# Terrarium_Schematic.net
KiCad netlist of a schematic drawn in EAGLE
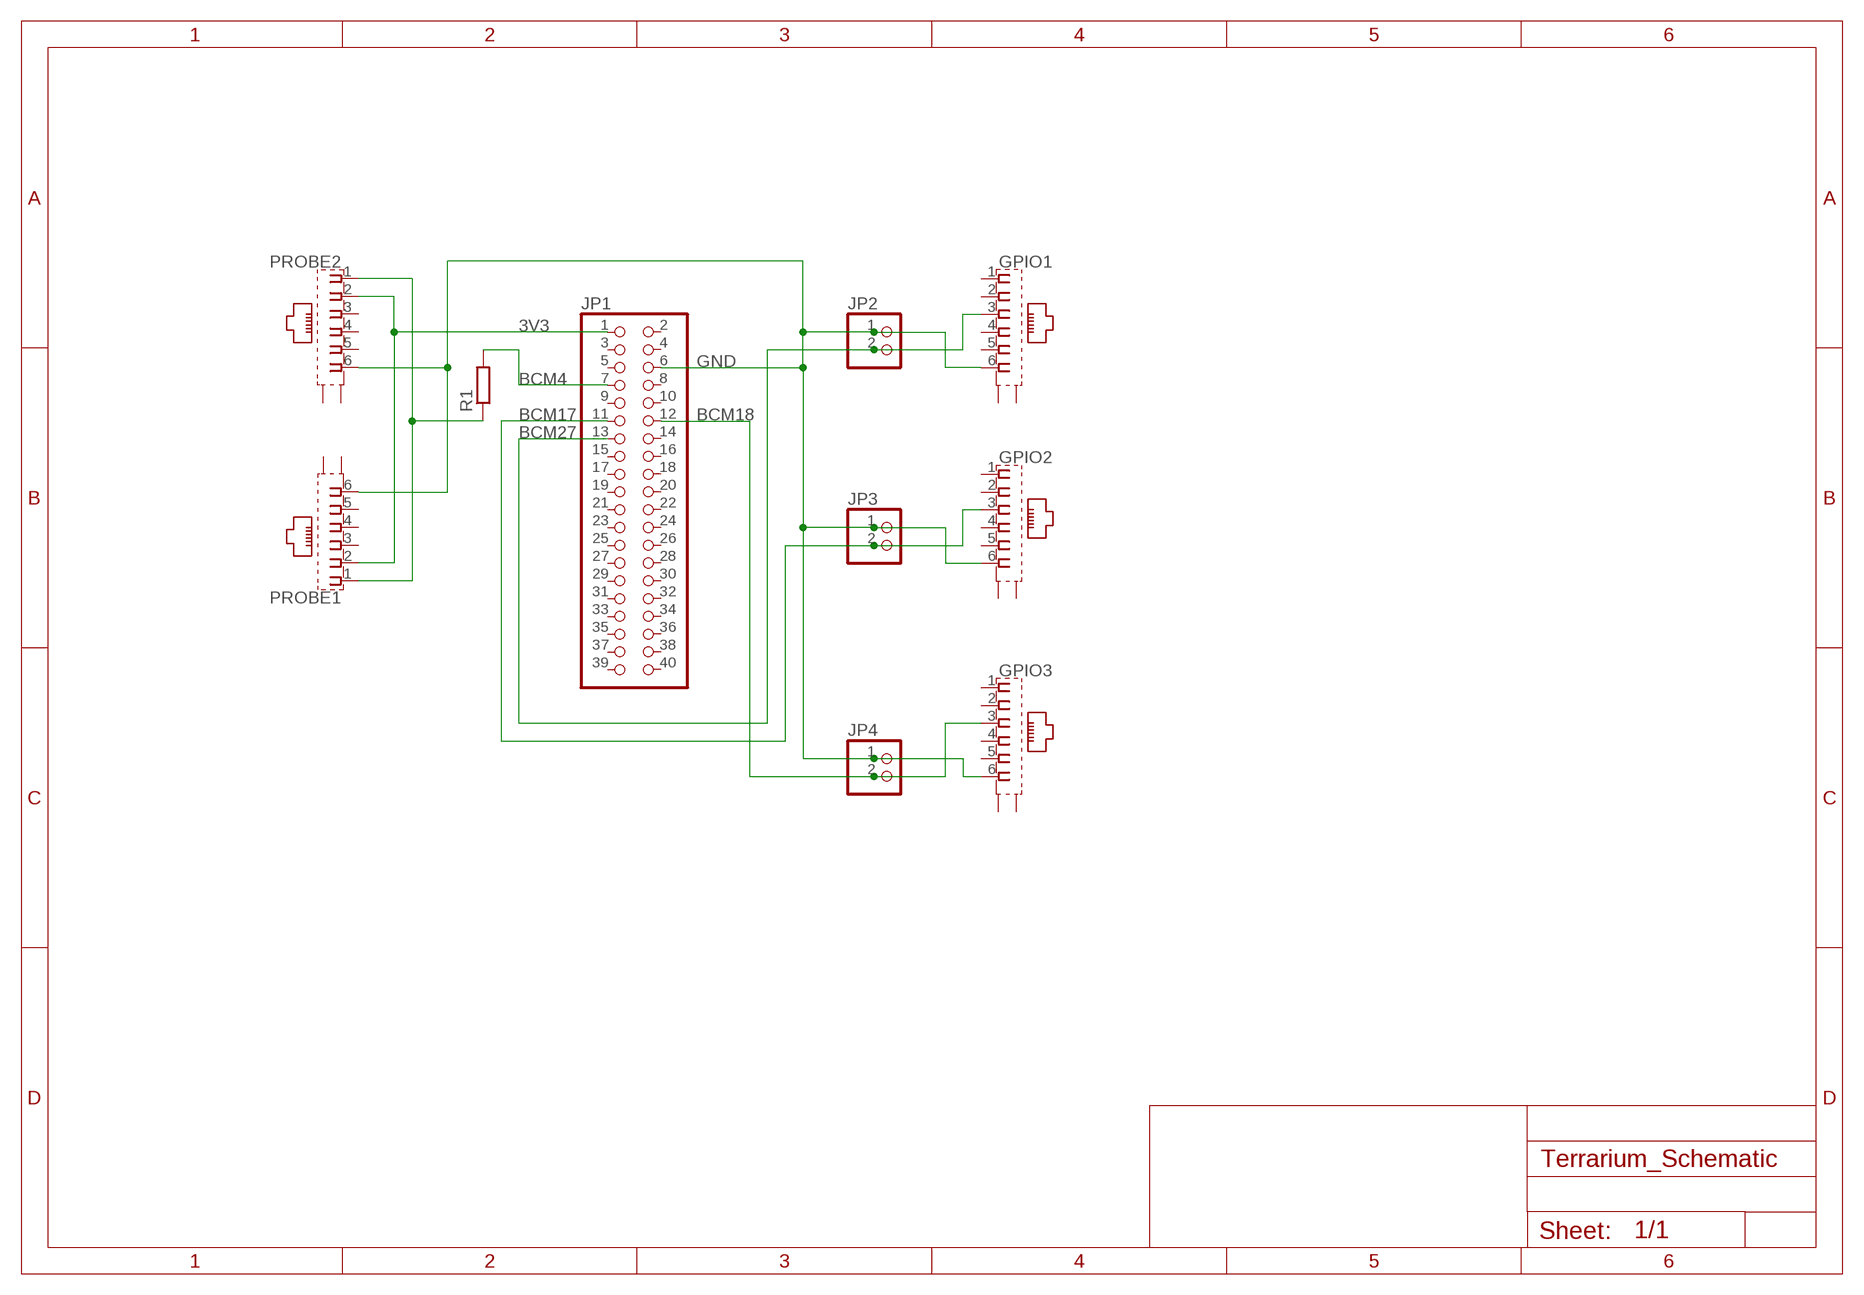
[diagram p0: schematic, sheet 1]

(export (version "E")
  (design (tool "Eeschema 10.0.6"))
  (components
    (comp (ref "GPIO1")
      (value "YH-55-10")
      (footprint "eagle-import:YH-55-10")
      (libsource (lib "eagle-import") (part "YH-55-10"))
    )
    (comp (ref "GPIO2")
      (value "YH-55-10")
      (footprint "eagle-import:YH-55-10")
      (libsource (lib "eagle-import") (part "YH-55-10"))
    )
    (comp (ref "GPIO3")
      (value "YH-55-10")
      (footprint "eagle-import:YH-55-10")
      (libsource (lib "eagle-import") (part "YH-55-10"))
    )
    (comp (ref "JP1")
      (value "PINHD-2X20")
      (footprint "eagle-import:2X20")
      (libsource (lib "eagle-import") (part "PINHD-2X20"))
    )
    (comp (ref "JP2")
      (value "PINHD-1X2")
      (footprint "eagle-import:1X02")
      (libsource (lib "eagle-import") (part "PINHD-1X2"))
    )
    (comp (ref "JP3")
      (value "PINHD-1X2")
      (footprint "eagle-import:1X02")
      (libsource (lib "eagle-import") (part "PINHD-1X2"))
    )
    (comp (ref "JP4")
      (value "PINHD-1X2")
      (footprint "eagle-import:1X02")
      (libsource (lib "eagle-import") (part "PINHD-1X2"))
    )
    (comp (ref "PROBE1")
      (value "YH-55-10")
      (footprint "eagle-import:YH-55-10")
      (libsource (lib "eagle-import") (part "YH-55-10"))
    )
    (comp (ref "PROBE2")
      (value "YH-55-10")
      (footprint "eagle-import:YH-55-10")
      (libsource (lib "eagle-import") (part "YH-55-10"))
    )
    (comp (ref "R1")
      (value "R-EU_0207/10")
      (footprint "eagle-import:0207_10")
      (libsource (lib "eagle-import") (part "R-EU_0207/10"))
    )
  )
  (nets
    (net (code "1") (name "/3V3") (class "Default")
      (node (ref "JP1") (pin "1") (pinfunction "1_1") (pintype "passive"))
      (node (ref "PROBE1") (pin "2") (pinfunction "2_2") (pintype "passive"))
      (node (ref "PROBE2") (pin "2") (pinfunction "2_2") (pintype "passive"))
    )
    (net (code "2") (name "/BCM4") (class "Default")
      (node (ref "JP1") (pin "7") (pinfunction "7_7") (pintype "passive"))
      (node (ref "R1") (pin "2") (pinfunction "2_2") (pintype "passive"))
    )
    (net (code "3") (name "/BCM17") (class "Default")
      (node (ref "GPIO2") (pin "3") (pinfunction "3_3") (pintype "passive"))
      (node (ref "JP1") (pin "11") (pinfunction "11_11") (pintype "passive"))
      (node (ref "JP3") (pin "2") (pinfunction "2_2") (pintype "passive"))
    )
    (net (code "4") (name "/BCM18") (class "Default")
      (node (ref "GPIO3") (pin "3") (pinfunction "3_3") (pintype "passive"))
      (node (ref "JP1") (pin "12") (pinfunction "12_12") (pintype "passive"))
      (node (ref "JP4") (pin "2") (pinfunction "2_2") (pintype "passive"))
    )
    (net (code "5") (name "/BCM27") (class "Default")
      (node (ref "GPIO1") (pin "3") (pinfunction "3_3") (pintype "passive"))
      (node (ref "JP1") (pin "13") (pinfunction "13_13") (pintype "passive"))
      (node (ref "JP2") (pin "2") (pinfunction "2_2") (pintype "passive"))
    )
    (net (code "6") (name "/GND") (class "Default")
      (node (ref "GPIO1") (pin "6") (pinfunction "6_6") (pintype "passive"))
      (node (ref "GPIO2") (pin "6") (pinfunction "6_6") (pintype "passive"))
      (node (ref "GPIO3") (pin "6") (pinfunction "6_6") (pintype "passive"))
      (node (ref "JP1") (pin "6") (pinfunction "6_6") (pintype "passive"))
      (node (ref "JP2") (pin "1") (pinfunction "1_1") (pintype "passive"))
      (node (ref "JP3") (pin "1") (pinfunction "1_1") (pintype "passive"))
      (node (ref "JP4") (pin "1") (pinfunction "1_1") (pintype "passive"))
      (node (ref "PROBE1") (pin "6") (pinfunction "6_6") (pintype "passive"))
      (node (ref "PROBE2") (pin "6") (pinfunction "6_6") (pintype "passive"))
    )
    (net (code "7") (name "Net-(PROBE1-Pad1)") (class "Default")
      (node (ref "PROBE1") (pin "1") (pinfunction "1_1") (pintype "passive"))
      (node (ref "PROBE2") (pin "1") (pinfunction "1_1") (pintype "passive"))
      (node (ref "R1") (pin "1") (pinfunction "1_1") (pintype "passive"))
    )
    (net (code "8") (name "unconnected-(GPIO1-Pad1)") (class "Default")
      (node (ref "GPIO1") (pin "1") (pinfunction "1_1") (pintype "passive"))
    )
    (net (code "9") (name "unconnected-(GPIO1-Pad2)") (class "Default")
      (node (ref "GPIO1") (pin "2") (pinfunction "2_2") (pintype "passive"))
    )
    (net (code "10") (name "unconnected-(GPIO1-Pad4)") (class "Default")
      (node (ref "GPIO1") (pin "4") (pinfunction "4_4") (pintype "passive"))
    )
    (net (code "11") (name "unconnected-(GPIO1-Pad5)") (class "Default")
      (node (ref "GPIO1") (pin "5") (pinfunction "5_5") (pintype "passive"))
    )
    (net (code "12") (name "unconnected-(GPIO1-S-PadS1)") (class "Default")
      (node (ref "GPIO1") (pin "S1") (pinfunction "S_S1") (pintype "passive"))
    )
    (net (code "13") (name "unconnected-(GPIO1-S-PadS2)") (class "Default")
      (node (ref "GPIO1") (pin "S2") (pinfunction "S_S2") (pintype "passive"))
    )
    (net (code "14") (name "unconnected-(GPIO2-Pad1)") (class "Default")
      (node (ref "GPIO2") (pin "1") (pinfunction "1_1") (pintype "passive"))
    )
    (net (code "15") (name "unconnected-(GPIO2-Pad2)") (class "Default")
      (node (ref "GPIO2") (pin "2") (pinfunction "2_2") (pintype "passive"))
    )
    (net (code "16") (name "unconnected-(GPIO2-Pad4)") (class "Default")
      (node (ref "GPIO2") (pin "4") (pinfunction "4_4") (pintype "passive"))
    )
    (net (code "17") (name "unconnected-(GPIO2-Pad5)") (class "Default")
      (node (ref "GPIO2") (pin "5") (pinfunction "5_5") (pintype "passive"))
    )
    (net (code "18") (name "unconnected-(GPIO2-S-PadS1)") (class "Default")
      (node (ref "GPIO2") (pin "S1") (pinfunction "S_S1") (pintype "passive"))
    )
    (net (code "19") (name "unconnected-(GPIO2-S-PadS2)") (class "Default")
      (node (ref "GPIO2") (pin "S2") (pinfunction "S_S2") (pintype "passive"))
    )
    (net (code "20") (name "unconnected-(GPIO3-Pad1)") (class "Default")
      (node (ref "GPIO3") (pin "1") (pinfunction "1_1") (pintype "passive"))
    )
    (net (code "21") (name "unconnected-(GPIO3-Pad2)") (class "Default")
      (node (ref "GPIO3") (pin "2") (pinfunction "2_2") (pintype "passive"))
    )
    (net (code "22") (name "unconnected-(GPIO3-Pad4)") (class "Default")
      (node (ref "GPIO3") (pin "4") (pinfunction "4_4") (pintype "passive"))
    )
    (net (code "23") (name "unconnected-(GPIO3-Pad5)") (class "Default")
      (node (ref "GPIO3") (pin "5") (pinfunction "5_5") (pintype "passive"))
    )
    (net (code "24") (name "unconnected-(GPIO3-S-PadS1)") (class "Default")
      (node (ref "GPIO3") (pin "S1") (pinfunction "S_S1") (pintype "passive"))
    )
    (net (code "25") (name "unconnected-(GPIO3-S-PadS2)") (class "Default")
      (node (ref "GPIO3") (pin "S2") (pinfunction "S_S2") (pintype "passive"))
    )
    (net (code "26") (name "unconnected-(JP1-Pad2)") (class "Default")
      (node (ref "JP1") (pin "2") (pinfunction "2_2") (pintype "passive"))
    )
    (net (code "27") (name "unconnected-(JP1-Pad3)") (class "Default")
      (node (ref "JP1") (pin "3") (pinfunction "3_3") (pintype "passive"))
    )
    (net (code "28") (name "unconnected-(JP1-Pad4)") (class "Default")
      (node (ref "JP1") (pin "4") (pinfunction "4_4") (pintype "passive"))
    )
    (net (code "29") (name "unconnected-(JP1-Pad5)") (class "Default")
      (node (ref "JP1") (pin "5") (pinfunction "5_5") (pintype "passive"))
    )
    (net (code "30") (name "unconnected-(JP1-Pad8)") (class "Default")
      (node (ref "JP1") (pin "8") (pinfunction "8_8") (pintype "passive"))
    )
    (net (code "31") (name "unconnected-(JP1-Pad9)") (class "Default")
      (node (ref "JP1") (pin "9") (pinfunction "9_9") (pintype "passive"))
    )
    (net (code "32") (name "unconnected-(JP1-Pad10)") (class "Default")
      (node (ref "JP1") (pin "10") (pinfunction "10_10") (pintype "passive"))
    )
    (net (code "33") (name "unconnected-(JP1-Pad14)") (class "Default")
      (node (ref "JP1") (pin "14") (pinfunction "14_14") (pintype "passive"))
    )
    (net (code "34") (name "unconnected-(JP1-Pad15)") (class "Default")
      (node (ref "JP1") (pin "15") (pinfunction "15_15") (pintype "passive"))
    )
    (net (code "35") (name "unconnected-(JP1-Pad16)") (class "Default")
      (node (ref "JP1") (pin "16") (pinfunction "16_16") (pintype "passive"))
    )
    (net (code "36") (name "unconnected-(JP1-Pad17)") (class "Default")
      (node (ref "JP1") (pin "17") (pinfunction "17_17") (pintype "passive"))
    )
    (net (code "37") (name "unconnected-(JP1-Pad18)") (class "Default")
      (node (ref "JP1") (pin "18") (pinfunction "18_18") (pintype "passive"))
    )
    (net (code "38") (name "unconnected-(JP1-Pad19)") (class "Default")
      (node (ref "JP1") (pin "19") (pinfunction "19_19") (pintype "passive"))
    )
    (net (code "39") (name "unconnected-(JP1-Pad20)") (class "Default")
      (node (ref "JP1") (pin "20") (pinfunction "20_20") (pintype "passive"))
    )
    (net (code "40") (name "unconnected-(JP1-Pad21)") (class "Default")
      (node (ref "JP1") (pin "21") (pinfunction "21_21") (pintype "passive"))
    )
    (net (code "41") (name "unconnected-(JP1-Pad22)") (class "Default")
      (node (ref "JP1") (pin "22") (pinfunction "22_22") (pintype "passive"))
    )
    (net (code "42") (name "unconnected-(JP1-Pad23)") (class "Default")
      (node (ref "JP1") (pin "23") (pinfunction "23_23") (pintype "passive"))
    )
    (net (code "43") (name "unconnected-(JP1-Pad24)") (class "Default")
      (node (ref "JP1") (pin "24") (pinfunction "24_24") (pintype "passive"))
    )
    (net (code "44") (name "unconnected-(JP1-Pad25)") (class "Default")
      (node (ref "JP1") (pin "25") (pinfunction "25_25") (pintype "passive"))
    )
    (net (code "45") (name "unconnected-(JP1-Pad26)") (class "Default")
      (node (ref "JP1") (pin "26") (pinfunction "26_26") (pintype "passive"))
    )
    (net (code "46") (name "unconnected-(JP1-Pad27)") (class "Default")
      (node (ref "JP1") (pin "27") (pinfunction "27_27") (pintype "passive"))
    )
    (net (code "47") (name "unconnected-(JP1-Pad28)") (class "Default")
      (node (ref "JP1") (pin "28") (pinfunction "28_28") (pintype "passive"))
    )
    (net (code "48") (name "unconnected-(JP1-Pad29)") (class "Default")
      (node (ref "JP1") (pin "29") (pinfunction "29_29") (pintype "passive"))
    )
    (net (code "49") (name "unconnected-(JP1-Pad30)") (class "Default")
      (node (ref "JP1") (pin "30") (pinfunction "30_30") (pintype "passive"))
    )
    (net (code "50") (name "unconnected-(JP1-Pad31)") (class "Default")
      (node (ref "JP1") (pin "31") (pinfunction "31_31") (pintype "passive"))
    )
    (net (code "51") (name "unconnected-(JP1-Pad32)") (class "Default")
      (node (ref "JP1") (pin "32") (pinfunction "32_32") (pintype "passive"))
    )
    (net (code "52") (name "unconnected-(JP1-Pad33)") (class "Default")
      (node (ref "JP1") (pin "33") (pinfunction "33_33") (pintype "passive"))
    )
    (net (code "53") (name "unconnected-(JP1-Pad34)") (class "Default")
      (node (ref "JP1") (pin "34") (pinfunction "34_34") (pintype "passive"))
    )
    (net (code "54") (name "unconnected-(JP1-Pad35)") (class "Default")
      (node (ref "JP1") (pin "35") (pinfunction "35_35") (pintype "passive"))
    )
    (net (code "55") (name "unconnected-(JP1-Pad36)") (class "Default")
      (node (ref "JP1") (pin "36") (pinfunction "36_36") (pintype "passive"))
    )
    (net (code "56") (name "unconnected-(JP1-Pad37)") (class "Default")
      (node (ref "JP1") (pin "37") (pinfunction "37_37") (pintype "passive"))
    )
    (net (code "57") (name "unconnected-(JP1-Pad38)") (class "Default")
      (node (ref "JP1") (pin "38") (pinfunction "38_38") (pintype "passive"))
    )
    (net (code "58") (name "unconnected-(JP1-Pad39)") (class "Default")
      (node (ref "JP1") (pin "39") (pinfunction "39_39") (pintype "passive"))
    )
    (net (code "59") (name "unconnected-(JP1-Pad40)") (class "Default")
      (node (ref "JP1") (pin "40") (pinfunction "40_40") (pintype "passive"))
    )
    (net (code "60") (name "unconnected-(PROBE1-Pad3)") (class "Default")
      (node (ref "PROBE1") (pin "3") (pinfunction "3_3") (pintype "passive"))
    )
    (net (code "61") (name "unconnected-(PROBE1-Pad4)") (class "Default")
      (node (ref "PROBE1") (pin "4") (pinfunction "4_4") (pintype "passive"))
    )
    (net (code "62") (name "unconnected-(PROBE1-Pad5)") (class "Default")
      (node (ref "PROBE1") (pin "5") (pinfunction "5_5") (pintype "passive"))
    )
    (net (code "63") (name "unconnected-(PROBE1-S-PadS1)") (class "Default")
      (node (ref "PROBE1") (pin "S1") (pinfunction "S_S1") (pintype "passive"))
    )
    (net (code "64") (name "unconnected-(PROBE1-S-PadS2)") (class "Default")
      (node (ref "PROBE1") (pin "S2") (pinfunction "S_S2") (pintype "passive"))
    )
    (net (code "65") (name "unconnected-(PROBE2-Pad3)") (class "Default")
      (node (ref "PROBE2") (pin "3") (pinfunction "3_3") (pintype "passive"))
    )
    (net (code "66") (name "unconnected-(PROBE2-Pad4)") (class "Default")
      (node (ref "PROBE2") (pin "4") (pinfunction "4_4") (pintype "passive"))
    )
    (net (code "67") (name "unconnected-(PROBE2-Pad5)") (class "Default")
      (node (ref "PROBE2") (pin "5") (pinfunction "5_5") (pintype "passive"))
    )
    (net (code "68") (name "unconnected-(PROBE2-S-PadS1)") (class "Default")
      (node (ref "PROBE2") (pin "S1") (pinfunction "S_S1") (pintype "passive"))
    )
    (net (code "69") (name "unconnected-(PROBE2-S-PadS2)") (class "Default")
      (node (ref "PROBE2") (pin "S2") (pinfunction "S_S2") (pintype "passive"))
    )
  )
)
